# SCH_Smart_Parking_IoT_2023-05-21.net
KiCad netlist of a schematic drawn in EasyEDA
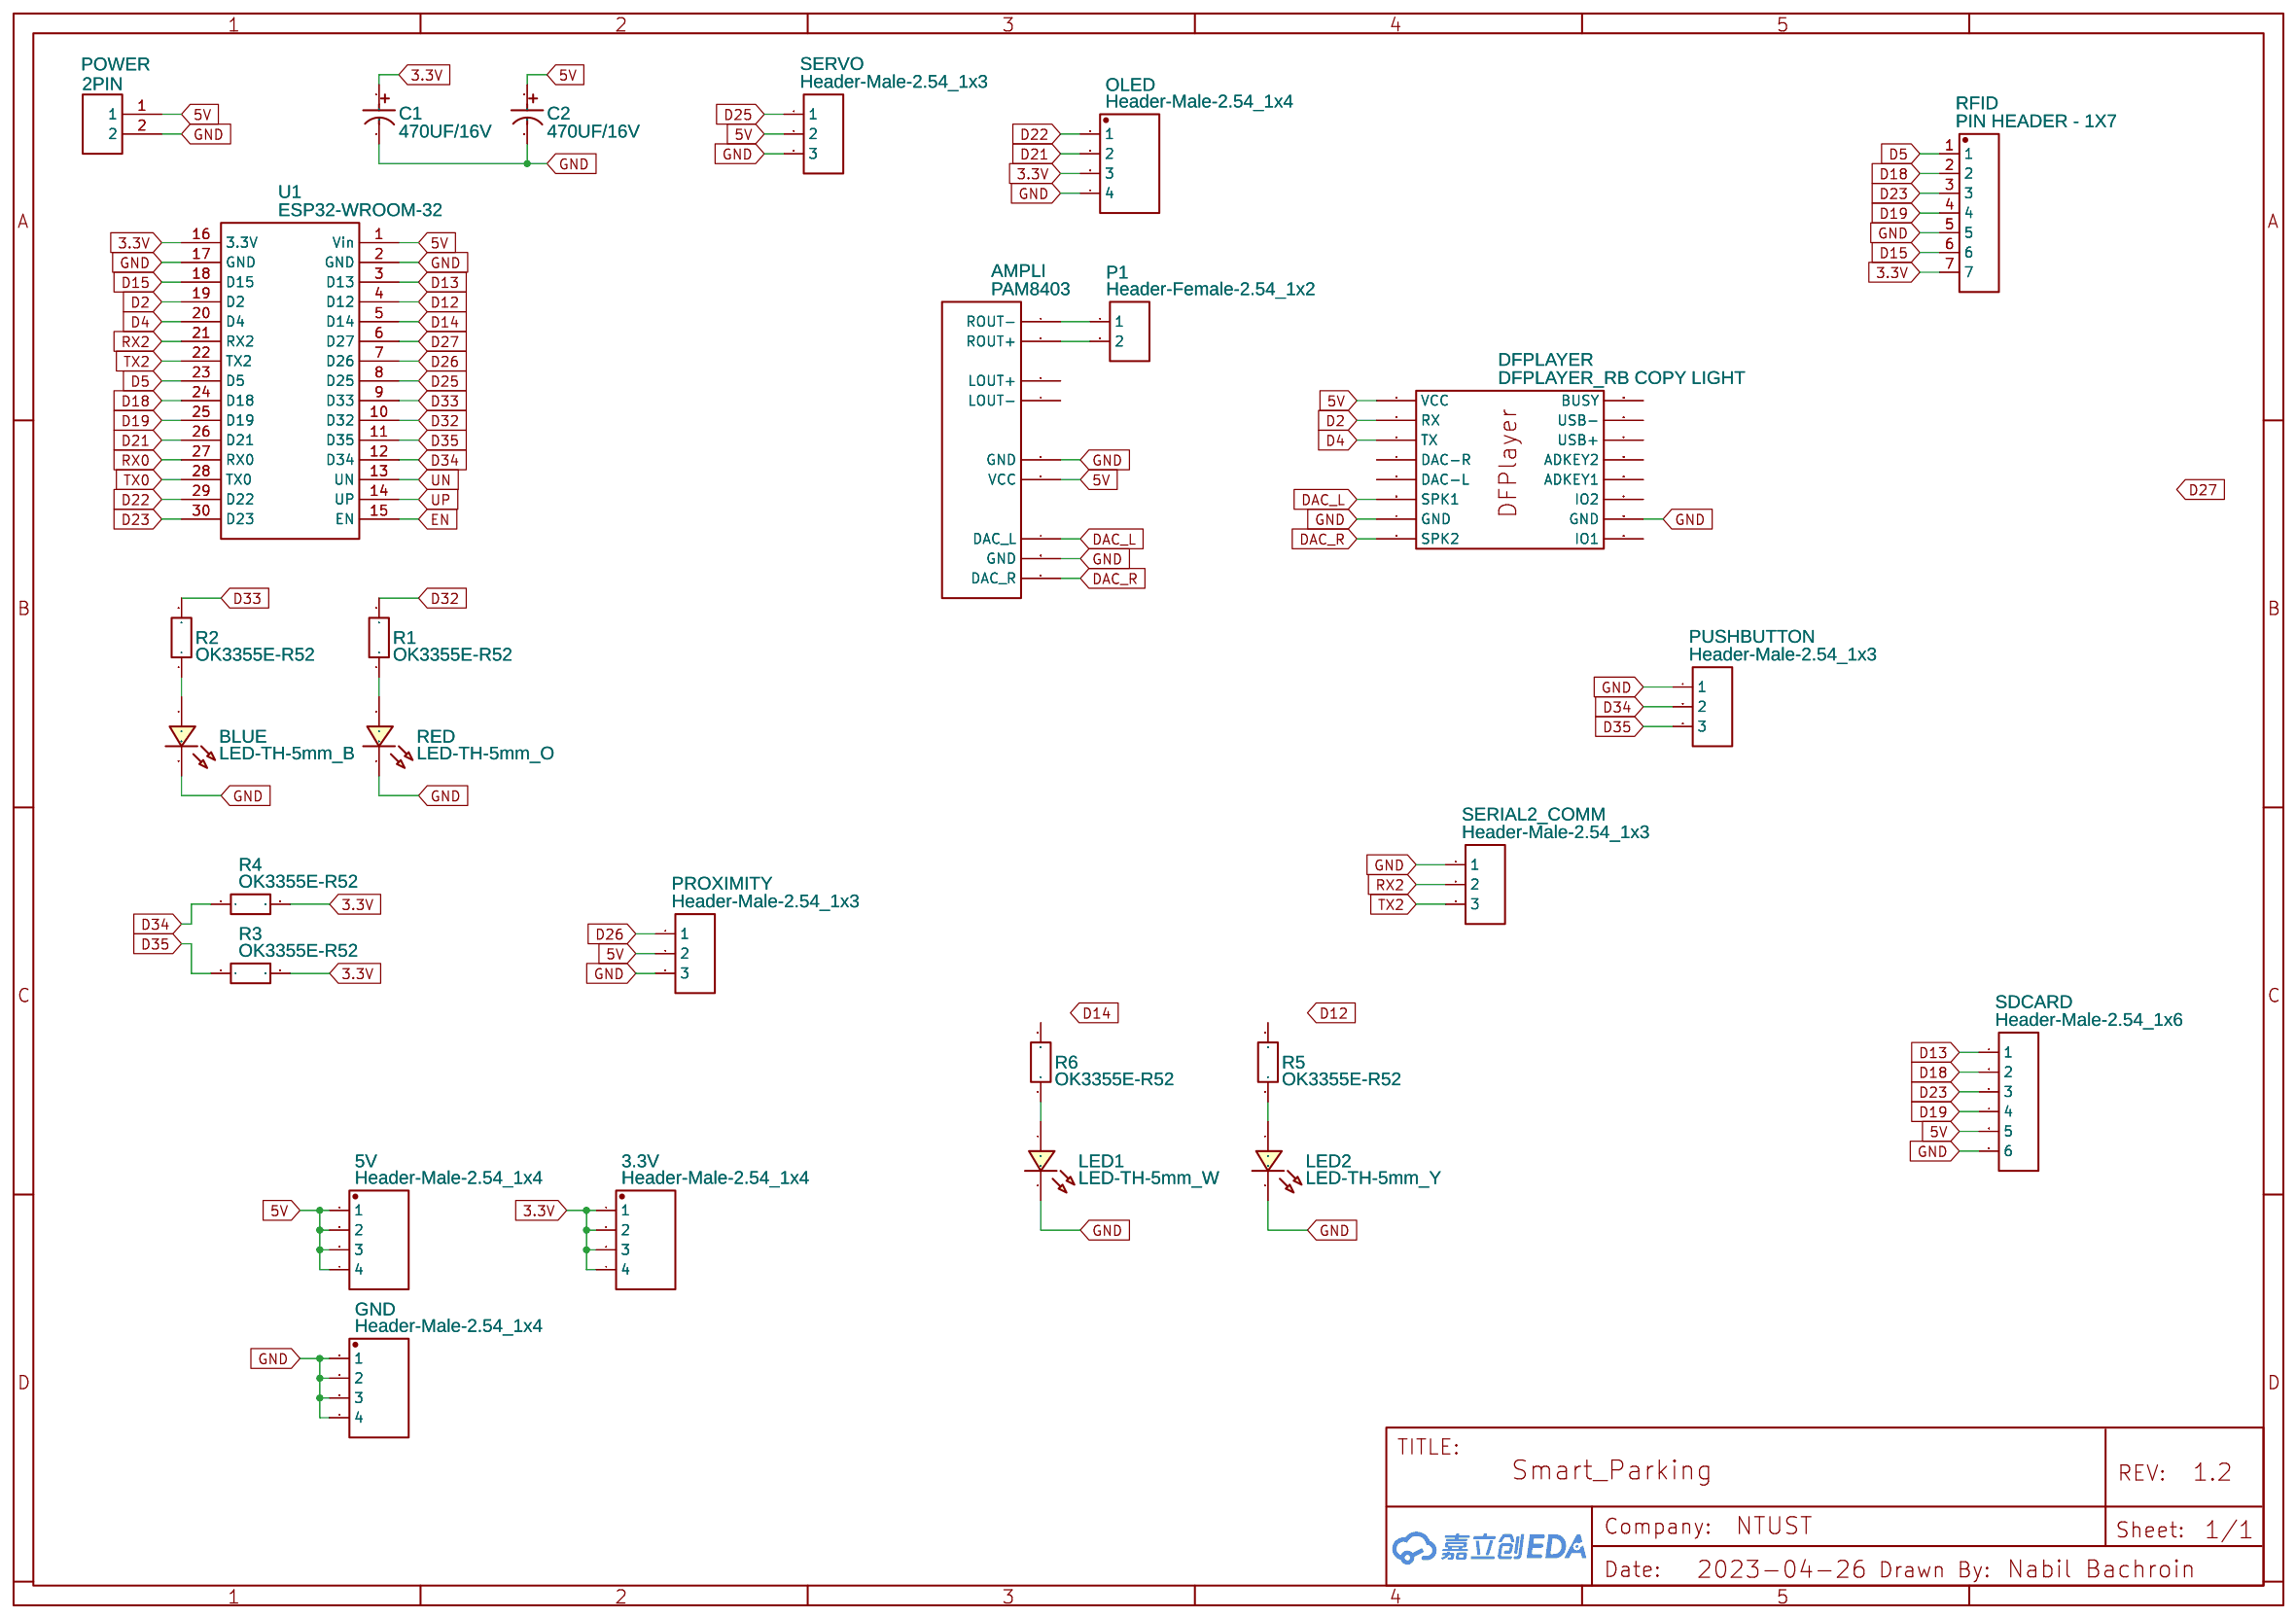
[diagram p0: schematic sheet]

(export (version "E")
  (design (tool "Eeschema 10.0.6"))
  (components
    (comp (ref "3.3V")
      (value "Header-Male-2.54_1x4")
      (fields
        (field (name "BOM_Manufacturer Part") "B-2100S04P-A110")
        (field (name "BOM_Supplier Part") "C124378")
      )
      (libsource (lib "") (part "Header-Male-2.54_1x4_1"))
    )
    (comp (ref "5V")
      (value "Header-Male-2.54_1x4")
      (fields
        (field (name "BOM_Manufacturer Part") "B-2100S04P-A110")
        (field (name "BOM_Supplier Part") "C124378")
      )
      (libsource (lib "") (part "Header-Male-2.54_1x4_3"))
    )
    (comp (ref "AMPLI") (value "PAM8403") (libsource (lib "") (part "PAM8403")))
    (comp (ref "BLUE") (value "LED-TH-5mm_B") (libsource (lib "") (part "LED-TH-5mm_B")))
    (comp (ref "C1")
      (value "470UF/16V")
      (fields
        (field (name "BOM_Manufacturer Part") "470uF/16V")
        (field (name "BOM_Supplier Part") "C9900008131")
      )
      (libsource (lib "") (part "470UF/16V"))
    )
    (comp (ref "C2")
      (value "470UF/16V")
      (fields
        (field (name "BOM_Manufacturer Part") "470uF/16V")
        (field (name "BOM_Supplier Part") "C9900008131")
      )
      (libsource (lib "") (part "470UF/16V"))
    )
    (comp (ref "DFPLAYER")
      (value "DFPLAYER_RB COPY LIGHT")
      (fields (field (name "BOM_Manufacturer Part") "DFPLAYER"))
      (libsource (lib "") (part "DFPLAYER_RB COPY LIGHT"))
    )
    (comp (ref "GND")
      (value "Header-Male-2.54_1x4")
      (fields
        (field (name "BOM_Manufacturer Part") "B-2100S04P-A110")
        (field (name "BOM_Supplier Part") "C124378")
      )
      (libsource (lib "") (part "Header-Male-2.54_1x4_2"))
    )
    (comp (ref "LED1") (value "LED-TH-5mm_W") (libsource (lib "") (part "LED-TH-5mm_W")))
    (comp (ref "LED2") (value "LED-TH-5mm_Y") (libsource (lib "") (part "LED-TH-5mm_Y")))
    (comp (ref "OLED")
      (value "Header-Male-2.54_1x4")
      (fields
        (field (name "BOM_Manufacturer Part") "B-2100S04P-A110")
        (field (name "BOM_Supplier Part") "C124378")
      )
      (libsource (lib "") (part "Header-Male-2.54_1x4"))
    )
    (comp (ref "P1")
      (value "Header-Female-2.54_1x2")
      (fields (field (name "BOM_Manufacturer Part") "2.54-1*2P母") (field (name "BOM_Supplier Part") "C49661"))
      (libsource (lib "") (part "Header-Female-2.54_1x2"))
    )
    (comp (ref "POWER")
      (value "2PIN")
      (fields (field (name "BOM_Manufacturer Part") "Pin_Header_2"))
      (libsource (lib "") (part "2PIN"))
    )
    (comp (ref "PROXIMITY")
      (value "Header-Male-2.54_1x3")
      (fields (field (name "BOM_Manufacturer Part") "2.54-1*3P针") (field (name "BOM_Supplier Part") "C49257"))
      (libsource (lib "") (part "Header-Male-2.54_1x3_3"))
    )
    (comp (ref "PUSHBUTTON")
      (value "Header-Male-2.54_1x3")
      (fields (field (name "BOM_Manufacturer Part") "2.54-1*3P针") (field (name "BOM_Supplier Part") "C49257"))
      (libsource (lib "") (part "Header-Male-2.54_1x3_1"))
    )
    (comp (ref "R1")
      (value "OK3355E-R52")
      (fields (field (name "BOM_Supplier Part") "C3522642"))
      (libsource (lib "") (part "OK3355E-R52"))
    )
    (comp (ref "R2")
      (value "OK3355E-R52")
      (fields (field (name "BOM_Supplier Part") "C3522642"))
      (libsource (lib "") (part "OK3355E-R52"))
    )
    (comp (ref "R3")
      (value "OK3355E-R52")
      (fields (field (name "BOM_Supplier Part") "C3522642"))
      (libsource (lib "") (part "OK3355E-R52_1"))
    )
    (comp (ref "R4")
      (value "OK3355E-R52")
      (fields (field (name "BOM_Supplier Part") "C3522642"))
      (libsource (lib "") (part "OK3355E-R52_1"))
    )
    (comp (ref "R5")
      (value "OK3355E-R52")
      (fields (field (name "BOM_Supplier Part") "C3522642"))
      (libsource (lib "") (part "OK3355E-R52"))
    )
    (comp (ref "R6")
      (value "OK3355E-R52")
      (fields (field (name "BOM_Supplier Part") "C3522642"))
      (libsource (lib "") (part "OK3355E-R52"))
    )
    (comp (ref "RED") (value "LED-TH-5mm_O") (libsource (lib "") (part "LED-TH-5mm_O")))
    (comp (ref "RFID") (value "PIN HEADER - 1X7") (libsource (lib "") (part "PIN HEADER - 1X7")))
    (comp (ref "SDCARD")
      (value "Header-Male-2.54_1x6")
      (fields
        (field (name "BOM_Manufacturer Part") "2.54-1x6P直针")
        (field (name "BOM_Supplier Part") "C37208")
      )
      (libsource (lib "") (part "Header-Male-2.54_1x6"))
    )
    (comp (ref "SERIAL2_COMM")
      (value "Header-Male-2.54_1x3")
      (fields (field (name "BOM_Manufacturer Part") "2.54-1*3P针") (field (name "BOM_Supplier Part") "C49257"))
      (libsource (lib "") (part "Header-Male-2.54_1x3_2"))
    )
    (comp (ref "SERVO")
      (value "Header-Male-2.54_1x3")
      (fields (field (name "BOM_Manufacturer Part") "2.54-1*3P针") (field (name "BOM_Supplier Part") "C49257"))
      (libsource (lib "") (part "Header-Male-2.54_1x3"))
    )
    (comp (ref "U1") (value "ESP32-WROOM-32") (libsource (lib "") (part "ESP32-WROOM-32")))
  )
  (nets
    (net (code "1") (name "3.3V") (class "Default")
      (node (ref "3.3V") (pin "1") (pinfunction "1_1") (pintype "unspecified"))
      (node (ref "3.3V") (pin "2") (pinfunction "2_2") (pintype "unspecified"))
      (node (ref "3.3V") (pin "3") (pinfunction "3_3") (pintype "unspecified"))
      (node (ref "3.3V") (pin "4") (pinfunction "4_4") (pintype "unspecified"))
      (node (ref "C1") (pin "1") (pinfunction "1_1") (pintype "input"))
      (node (ref "OLED") (pin "3") (pinfunction "3_3") (pintype "unspecified"))
      (node (ref "R3") (pin "2") (pinfunction "2_2") (pintype "unspecified"))
      (node (ref "R4") (pin "2") (pinfunction "2_2") (pintype "unspecified"))
      (node (ref "RFID") (pin "7") (pinfunction "7_7") (pintype "unspecified"))
      (node (ref "U1") (pin "16") (pinfunction "3.3V_16") (pintype "unspecified"))
    )
    (net (code "2") (name "5V") (class "Default")
      (node (ref "5V") (pin "1") (pinfunction "1_1") (pintype "unspecified"))
      (node (ref "5V") (pin "2") (pinfunction "2_2") (pintype "unspecified"))
      (node (ref "5V") (pin "3") (pinfunction "3_3") (pintype "unspecified"))
      (node (ref "5V") (pin "4") (pinfunction "4_4") (pintype "unspecified"))
      (node (ref "AMPLI") (pin "6") (pinfunction "VCC_6") (pintype "unspecified"))
      (node (ref "C2") (pin "1") (pinfunction "1_1") (pintype "input"))
      (node (ref "DFPLAYER") (pin "1") (pinfunction "VCC_1") (pintype "unspecified"))
      (node (ref "POWER") (pin "1") (pinfunction "1_1") (pintype "unspecified"))
      (node (ref "PROXIMITY") (pin "2") (pinfunction "2_2") (pintype "input"))
      (node (ref "SDCARD") (pin "5") (pinfunction "5_5") (pintype "input"))
      (node (ref "SERVO") (pin "2") (pinfunction "2_2") (pintype "input"))
      (node (ref "U1") (pin "1") (pinfunction "Vin_1") (pintype "unspecified"))
    )
    (net (code "3") (name "D2") (class "Default")
      (node (ref "DFPLAYER") (pin "2") (pinfunction "RX_2") (pintype "unspecified"))
      (node (ref "U1") (pin "19") (pinfunction "D2_19") (pintype "unspecified"))
    )
    (net (code "4") (name "D4") (class "Default")
      (node (ref "DFPLAYER") (pin "3") (pinfunction "TX_3") (pintype "unspecified"))
      (node (ref "U1") (pin "20") (pinfunction "D4_20") (pintype "unspecified"))
    )
    (net (code "5") (name "D5") (class "Default")
      (node (ref "RFID") (pin "1") (pinfunction "1_1") (pintype "unspecified"))
      (node (ref "U1") (pin "23") (pinfunction "D5_23") (pintype "unspecified"))
    )
    (net (code "6") (name "D12") (class "Default")
      (node (ref "U1") (pin "4") (pinfunction "D12_4") (pintype "unspecified"))
    )
    (net (code "7") (name "D13") (class "Default")
      (node (ref "SDCARD") (pin "1") (pinfunction "1_1") (pintype "input"))
      (node (ref "U1") (pin "3") (pinfunction "D13_3") (pintype "unspecified"))
    )
    (net (code "8") (name "D14") (class "Default")
      (node (ref "U1") (pin "5") (pinfunction "D14_5") (pintype "unspecified"))
    )
    (net (code "9") (name "D15") (class "Default")
      (node (ref "RFID") (pin "6") (pinfunction "6_6") (pintype "unspecified"))
      (node (ref "U1") (pin "18") (pinfunction "D15_18") (pintype "unspecified"))
    )
    (net (code "10") (name "D18") (class "Default")
      (node (ref "RFID") (pin "2") (pinfunction "2_2") (pintype "unspecified"))
      (node (ref "SDCARD") (pin "2") (pinfunction "2_2") (pintype "input"))
      (node (ref "U1") (pin "24") (pinfunction "D18_24") (pintype "unspecified"))
    )
    (net (code "11") (name "D19") (class "Default")
      (node (ref "RFID") (pin "4") (pinfunction "4_4") (pintype "unspecified"))
      (node (ref "SDCARD") (pin "4") (pinfunction "4_4") (pintype "input"))
      (node (ref "U1") (pin "25") (pinfunction "D19_25") (pintype "unspecified"))
    )
    (net (code "12") (name "D21") (class "Default")
      (node (ref "OLED") (pin "2") (pinfunction "2_2") (pintype "unspecified"))
      (node (ref "U1") (pin "26") (pinfunction "D21_26") (pintype "unspecified"))
    )
    (net (code "13") (name "D22") (class "Default")
      (node (ref "OLED") (pin "1") (pinfunction "1_1") (pintype "unspecified"))
      (node (ref "U1") (pin "29") (pinfunction "D22_29") (pintype "unspecified"))
    )
    (net (code "14") (name "D23") (class "Default")
      (node (ref "RFID") (pin "3") (pinfunction "3_3") (pintype "unspecified"))
      (node (ref "SDCARD") (pin "3") (pinfunction "3_3") (pintype "input"))
      (node (ref "U1") (pin "30") (pinfunction "D23_30") (pintype "unspecified"))
    )
    (net (code "15") (name "D25") (class "Default")
      (node (ref "SERVO") (pin "1") (pinfunction "1_1") (pintype "input"))
      (node (ref "U1") (pin "8") (pinfunction "D25_8") (pintype "unspecified"))
    )
    (net (code "16") (name "D26") (class "Default")
      (node (ref "PROXIMITY") (pin "1") (pinfunction "1_1") (pintype "input"))
      (node (ref "U1") (pin "7") (pinfunction "D26_7") (pintype "unspecified"))
    )
    (net (code "17") (name "D27") (class "Default")
      (node (ref "U1") (pin "6") (pinfunction "D27_6") (pintype "unspecified"))
    )
    (net (code "18") (name "D32") (class "Default")
      (node (ref "R1") (pin "2") (pinfunction "2_2") (pintype "unspecified"))
      (node (ref "U1") (pin "10") (pinfunction "D32_10") (pintype "unspecified"))
    )
    (net (code "19") (name "D33") (class "Default")
      (node (ref "R2") (pin "2") (pinfunction "2_2") (pintype "unspecified"))
      (node (ref "U1") (pin "9") (pinfunction "D33_9") (pintype "unspecified"))
    )
    (net (code "20") (name "D34") (class "Default")
      (node (ref "PUSHBUTTON") (pin "2") (pinfunction "2_2") (pintype "input"))
      (node (ref "R4") (pin "1") (pinfunction "1_1") (pintype "unspecified"))
      (node (ref "U1") (pin "12") (pinfunction "D34_12") (pintype "unspecified"))
    )
    (net (code "21") (name "D35") (class "Default")
      (node (ref "PUSHBUTTON") (pin "3") (pinfunction "3_3") (pintype "input"))
      (node (ref "R3") (pin "1") (pinfunction "1_1") (pintype "unspecified"))
      (node (ref "U1") (pin "11") (pinfunction "D35_11") (pintype "unspecified"))
    )
    (net (code "22") (name "DAC_L") (class "Default")
      (node (ref "AMPLI") (pin "7") (pinfunction "DAC_L_7") (pintype "unspecified"))
      (node (ref "DFPLAYER") (pin "6") (pinfunction "SPK1_6") (pintype "unspecified"))
    )
    (net (code "23") (name "DAC_R") (class "Default")
      (node (ref "AMPLI") (pin "9") (pinfunction "DAC_R_9") (pintype "unspecified"))
      (node (ref "DFPLAYER") (pin "8") (pinfunction "SPK2_8") (pintype "unspecified"))
    )
    (net (code "24") (name "EN") (class "Default")
      (node (ref "U1") (pin "15") (pinfunction "EN_15") (pintype "unspecified"))
    )
    (net (code "25") (name "GND") (class "Default")
      (node (ref "AMPLI") (pin "5") (pinfunction "GND_5") (pintype "unspecified"))
      (node (ref "AMPLI") (pin "8") (pinfunction "GND_8") (pintype "unspecified"))
      (node (ref "BLUE") (pin "2") (pinfunction "2_2") (pintype "unspecified"))
      (node (ref "C1") (pin "2") (pinfunction "2_2") (pintype "input"))
      (node (ref "C2") (pin "2") (pinfunction "2_2") (pintype "input"))
      (node (ref "DFPLAYER") (pin "10") (pinfunction "GND_10") (pintype "unspecified"))
      (node (ref "DFPLAYER") (pin "7") (pinfunction "GND_7") (pintype "unspecified"))
      (node (ref "GND") (pin "1") (pinfunction "1_1") (pintype "unspecified"))
      (node (ref "GND") (pin "2") (pinfunction "2_2") (pintype "unspecified"))
      (node (ref "GND") (pin "3") (pinfunction "3_3") (pintype "unspecified"))
      (node (ref "GND") (pin "4") (pinfunction "4_4") (pintype "unspecified"))
      (node (ref "LED1") (pin "2") (pinfunction "2_2") (pintype "unspecified"))
      (node (ref "LED2") (pin "2") (pinfunction "2_2") (pintype "unspecified"))
      (node (ref "OLED") (pin "4") (pinfunction "4_4") (pintype "unspecified"))
      (node (ref "POWER") (pin "2") (pinfunction "2_2") (pintype "unspecified"))
      (node (ref "PROXIMITY") (pin "3") (pinfunction "3_3") (pintype "input"))
      (node (ref "PUSHBUTTON") (pin "1") (pinfunction "1_1") (pintype "input"))
      (node (ref "RED") (pin "2") (pinfunction "2_2") (pintype "unspecified"))
      (node (ref "RFID") (pin "5") (pinfunction "5_5") (pintype "unspecified"))
      (node (ref "SDCARD") (pin "6") (pinfunction "6_6") (pintype "input"))
      (node (ref "SERIAL2_COMM") (pin "1") (pinfunction "1_1") (pintype "input"))
      (node (ref "SERVO") (pin "3") (pinfunction "3_3") (pintype "input"))
      (node (ref "U1") (pin "17") (pinfunction "GND_17") (pintype "unspecified"))
      (node (ref "U1") (pin "2") (pinfunction "GND_2") (pintype "unspecified"))
    )
    (net (code "26") (name "Net-(AMPLI-ROUT+)") (class "Default")
      (node (ref "AMPLI") (pin "2") (pinfunction "ROUT+_2") (pintype "unspecified"))
      (node (ref "P1") (pin "2") (pinfunction "2_2") (pintype "input"))
    )
    (net (code "27") (name "Net-(AMPLI-ROUT-)") (class "Default")
      (node (ref "AMPLI") (pin "1") (pinfunction "ROUT-_1") (pintype "unspecified"))
      (node (ref "P1") (pin "1") (pinfunction "1_1") (pintype "input"))
    )
    (net (code "28") (name "Net-(BLUE-Pad1)") (class "Default")
      (node (ref "BLUE") (pin "1") (pinfunction "1_1") (pintype "unspecified"))
      (node (ref "R2") (pin "1") (pinfunction "1_1") (pintype "unspecified"))
    )
    (net (code "29") (name "Net-(LED1-Pad1)") (class "Default")
      (node (ref "LED1") (pin "1") (pinfunction "1_1") (pintype "unspecified"))
      (node (ref "R6") (pin "1") (pinfunction "1_1") (pintype "unspecified"))
    )
    (net (code "30") (name "Net-(LED2-Pad1)") (class "Default")
      (node (ref "LED2") (pin "1") (pinfunction "1_1") (pintype "unspecified"))
      (node (ref "R5") (pin "1") (pinfunction "1_1") (pintype "unspecified"))
    )
    (net (code "31") (name "Net-(R1-Pad1)") (class "Default")
      (node (ref "R1") (pin "1") (pinfunction "1_1") (pintype "unspecified"))
      (node (ref "RED") (pin "1") (pinfunction "1_1") (pintype "unspecified"))
    )
    (net (code "32") (name "RX0") (class "Default")
      (node (ref "U1") (pin "27") (pinfunction "RX0_27") (pintype "unspecified"))
    )
    (net (code "33") (name "RX2") (class "Default")
      (node (ref "SERIAL2_COMM") (pin "2") (pinfunction "2_2") (pintype "input"))
      (node (ref "U1") (pin "21") (pinfunction "RX2_21") (pintype "unspecified"))
    )
    (net (code "34") (name "TX0") (class "Default")
      (node (ref "U1") (pin "28") (pinfunction "TX0_28") (pintype "unspecified"))
    )
    (net (code "35") (name "TX2") (class "Default")
      (node (ref "SERIAL2_COMM") (pin "3") (pinfunction "3_3") (pintype "input"))
      (node (ref "U1") (pin "22") (pinfunction "TX2_22") (pintype "unspecified"))
    )
    (net (code "36") (name "UN") (class "Default")
      (node (ref "U1") (pin "13") (pinfunction "UN_13") (pintype "unspecified"))
    )
    (net (code "37") (name "UP") (class "Default")
      (node (ref "U1") (pin "14") (pinfunction "UP_14") (pintype "unspecified"))
    )
    (net (code "38") (name "unconnected-(AMPLI-LOUT+-Pad3)") (class "Default")
      (node (ref "AMPLI") (pin "3") (pinfunction "LOUT+_3") (pintype "unspecified"))
    )
    (net (code "39") (name "unconnected-(AMPLI-LOUT--Pad4)") (class "Default")
      (node (ref "AMPLI") (pin "4") (pinfunction "LOUT-_4") (pintype "unspecified"))
    )
    (net (code "40") (name "unconnected-(DFPLAYER-ADKEY1-Pad12)") (class "Default")
      (node (ref "DFPLAYER") (pin "12") (pinfunction "ADKEY1_12") (pintype "unspecified"))
    )
    (net (code "41") (name "unconnected-(DFPLAYER-ADKEY2-Pad13)") (class "Default")
      (node (ref "DFPLAYER") (pin "13") (pinfunction "ADKEY2_13") (pintype "unspecified"))
    )
    (net (code "42") (name "unconnected-(DFPLAYER-BUSY-Pad16)") (class "Default")
      (node (ref "DFPLAYER") (pin "16") (pinfunction "BUSY_16") (pintype "unspecified"))
    )
    (net (code "43") (name "unconnected-(DFPLAYER-DAC-L-Pad5)") (class "Default")
      (node (ref "DFPLAYER") (pin "5") (pinfunction "DAC-L_5") (pintype "unspecified"))
    )
    (net (code "44") (name "unconnected-(DFPLAYER-DAC-R-Pad4)") (class "Default")
      (node (ref "DFPLAYER") (pin "4") (pinfunction "DAC-R_4") (pintype "unspecified"))
    )
    (net (code "45") (name "unconnected-(DFPLAYER-IO1-Pad9)") (class "Default")
      (node (ref "DFPLAYER") (pin "9") (pinfunction "IO1_9") (pintype "unspecified"))
    )
    (net (code "46") (name "unconnected-(DFPLAYER-IO2-Pad11)") (class "Default")
      (node (ref "DFPLAYER") (pin "11") (pinfunction "IO2_11") (pintype "unspecified"))
    )
    (net (code "47") (name "unconnected-(DFPLAYER-USB+-Pad14)") (class "Default")
      (node (ref "DFPLAYER") (pin "14") (pinfunction "USB+_14") (pintype "unspecified"))
    )
    (net (code "48") (name "unconnected-(DFPLAYER-USB--Pad15)") (class "Default")
      (node (ref "DFPLAYER") (pin "15") (pinfunction "USB-_15") (pintype "unspecified"))
    )
    (net (code "49") (name "unconnected-(R5-Pad2)") (class "Default")
      (node (ref "R5") (pin "2") (pinfunction "2_2") (pintype "unspecified"))
    )
    (net (code "50") (name "unconnected-(R6-Pad2)") (class "Default")
      (node (ref "R6") (pin "2") (pinfunction "2_2") (pintype "unspecified"))
    )
  )
)
